# 3310.net
KiCad netlist of a schematic drawn in EAGLE
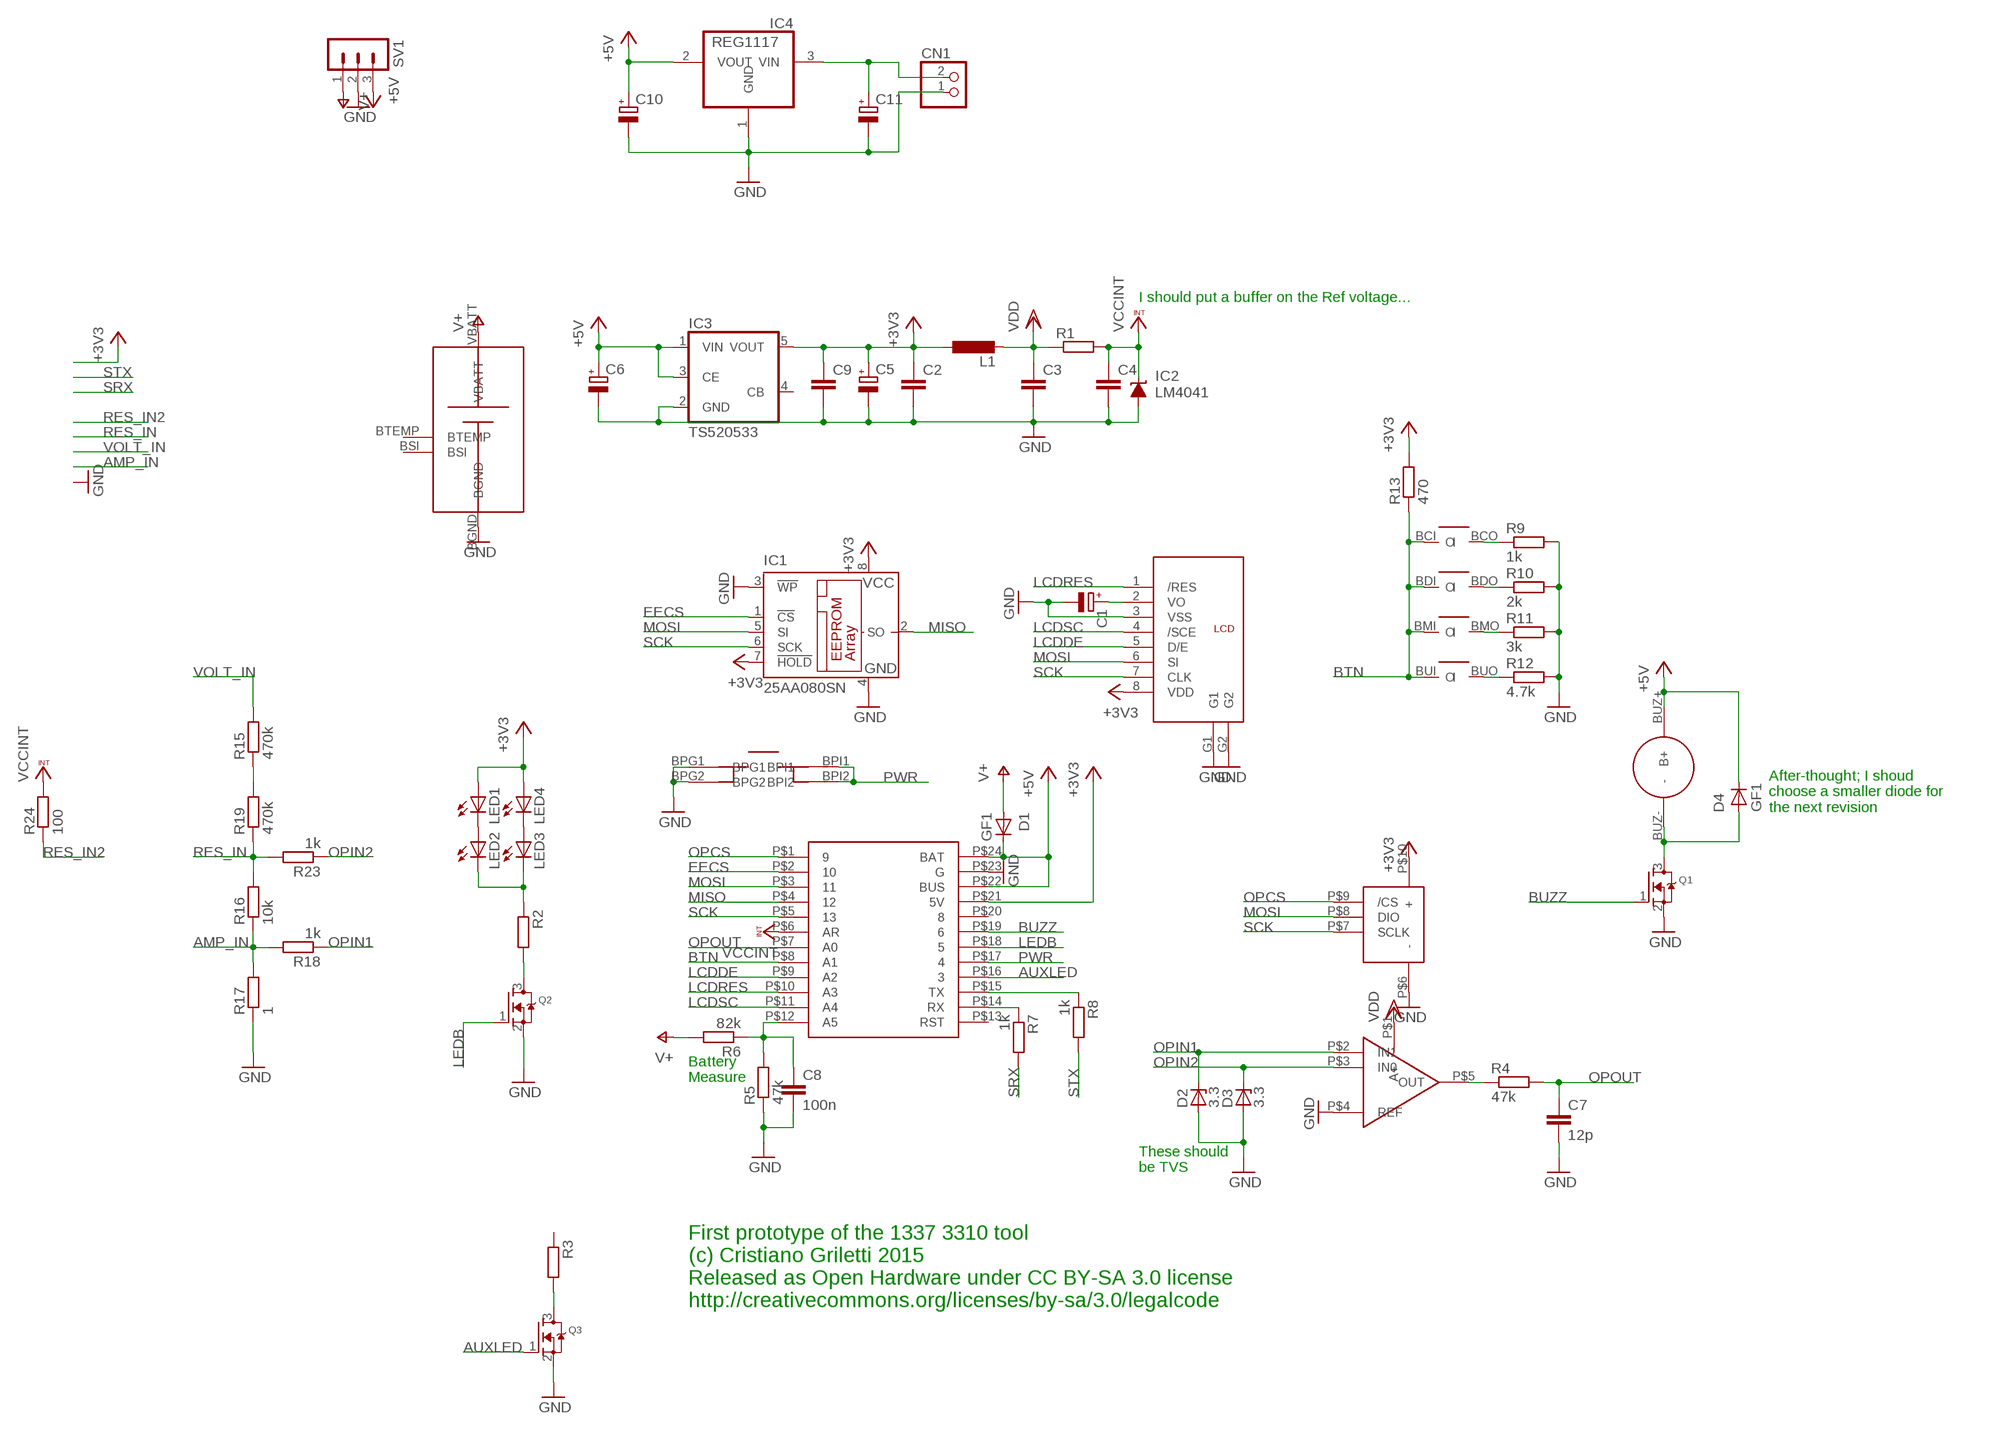
[diagram p0: schematic, sheet 1]

(export (version "E")
  (design (tool "Eeschema 10.0.6"))
  (components
    (comp (ref "C1")
      (value "CPOL-EUC/6032-28R")
      (footprint "eagle-import:C_6032-28R")
      (libsource (lib "eagle-import") (part "CPOL-EUC/6032-28R"))
    )
    (comp (ref "C2")
      (value "C-EUC0805K")
      (footprint "eagle-import:C0805K")
      (libsource (lib "eagle-import") (part "C-EUC0805K"))
    )
    (comp (ref "C3")
      (value "C-EUC0805K")
      (footprint "eagle-import:C0805K")
      (libsource (lib "eagle-import") (part "C-EUC0805K"))
    )
    (comp (ref "C4")
      (value "C-EUC0805K")
      (footprint "eagle-import:C0805K")
      (libsource (lib "eagle-import") (part "C-EUC0805K"))
    )
    (comp (ref "C5")
      (value "CPOL-EUB/3528-21R")
      (footprint "eagle-import:B_3528-21R")
      (libsource (lib "eagle-import") (part "CPOL-EUB/3528-21R"))
    )
    (comp (ref "C6")
      (value "CPOL-EUB/3528-21R")
      (footprint "eagle-import:B_3528-21R")
      (libsource (lib "eagle-import") (part "CPOL-EUB/3528-21R"))
    )
    (comp (ref "C7")
      (value "12p")
      (footprint "eagle-import:C0805K")
      (libsource (lib "eagle-import") (part "C-EUC0805K"))
    )
    (comp (ref "C8")
      (value "100n")
      (footprint "eagle-import:C0805K")
      (libsource (lib "eagle-import") (part "C-EUC0805K"))
    )
    (comp (ref "C9")
      (value "C-EUC0805K")
      (footprint "eagle-import:C0805K")
      (libsource (lib "eagle-import") (part "C-EUC0805K"))
    )
    (comp (ref "C10")
      (value "CPOL-EUB/3528-21R")
      (footprint "eagle-import:B_3528-21R")
      (libsource (lib "eagle-import") (part "CPOL-EUB/3528-21R"))
    )
    (comp (ref "C11")
      (value "CPOL-EUB/3528-21R")
      (footprint "eagle-import:B_3528-21R")
      (libsource (lib "eagle-import") (part "CPOL-EUB/3528-21R"))
    )
    (comp (ref "CN1")
      (value "JST_2PIN-SMT")
      (footprint "eagle-import:JST-PH-2-SMT")
      (libsource (lib "eagle-import") (part "JST_2PIN-SMT"))
    )
    (comp (ref "D1")
      (value "GF1")
      (footprint "eagle-import:SMA-DO214AC")
      (libsource (lib "eagle-import") (part "GF1"))
    )
    (comp (ref "D2")
      (value "3.3")
      (footprint "eagle-import:SOD80C")
      (libsource (lib "eagle-import") (part "ZENER-DIODESOD80C"))
    )
    (comp (ref "D3")
      (value "3.3")
      (footprint "eagle-import:SOD80C")
      (libsource (lib "eagle-import") (part "ZENER-DIODESOD80C"))
    )
    (comp (ref "D4")
      (value "GF1")
      (footprint "eagle-import:SMA-DO214AC")
      (libsource (lib "eagle-import") (part "GF1"))
    )
    (comp (ref "IC1")
      (value "25AA080SN")
      (footprint "eagle-import:SO-08")
      (fields (field (name "MF") "MICROCHIP") (field (name "MPN") "25AA080/SN"))
      (libsource (lib "eagle-import") (part "25SNAA080"))
    )
    (comp (ref "IC2")
      (value "LM4041")
      (footprint "eagle-import:DBZ_R-PDSO-G3")
      (fields (field (name "MPN") "LM4041A12IDBZR"))
      (libsource (lib "eagle-import") (part "LM4041DBZA12"))
    )
    (comp (ref "IC3")
      (value "TS520533")
      (footprint "eagle-import:SOT25")
      (libsource (lib "eagle-import") (part "TS520533"))
    )
    (comp (ref "IC4")
      (value "REG1117")
      (footprint "eagle-import:SOT223")
      (libsource (lib "eagle-import") (part "REG1117"))
    )
    (comp (ref "L1")
      (value "L-EUL3216C")
      (footprint "eagle-import:L3216C")
      (libsource (lib "eagle-import") (part "L-EUL3216C"))
    )
    (comp (ref "LED1")
      (value "LEDCHIPLED_0603")
      (footprint "eagle-import:CHIPLED_0603")
      (libsource (lib "eagle-import") (part "LEDCHIPLED_0603"))
    )
    (comp (ref "LED2")
      (value "LEDCHIPLED_0603")
      (footprint "eagle-import:CHIPLED_0603")
      (libsource (lib "eagle-import") (part "LEDCHIPLED_0603"))
    )
    (comp (ref "LED3")
      (value "LEDCHIPLED_0603")
      (footprint "eagle-import:CHIPLED_0603")
      (libsource (lib "eagle-import") (part "LEDCHIPLED_0603"))
    )
    (comp (ref "LED4")
      (value "LEDCHIPLED_0603")
      (footprint "eagle-import:CHIPLED_0603")
      (libsource (lib "eagle-import") (part "LEDCHIPLED_0603"))
    )
    (comp (ref "Q1")
      (value "MOSFET-NREFLOW")
      (footprint "eagle-import:SOT23")
      (libsource (lib "eagle-import") (part "MOSFET-NREFLOW"))
    )
    (comp (ref "Q2")
      (value "MOSFET-NREFLOW")
      (footprint "eagle-import:SOT23")
      (libsource (lib "eagle-import") (part "MOSFET-NREFLOW"))
    )
    (comp (ref "Q3")
      (value "MOSFET-NREFLOW")
      (footprint "eagle-import:SOT23")
      (libsource (lib "eagle-import") (part "MOSFET-NREFLOW"))
    )
    (comp (ref "R1")
      (value "R-EU_R0805")
      (footprint "eagle-import:R0805")
      (libsource (lib "eagle-import") (part "R-EU_R0805"))
    )
    (comp (ref "R2")
      (value "R-EU_R0805")
      (footprint "eagle-import:R0805")
      (libsource (lib "eagle-import") (part "R-EU_R0805"))
    )
    (comp (ref "R3")
      (value "R-EU_R0805")
      (footprint "eagle-import:R0805")
      (libsource (lib "eagle-import") (part "R-EU_R0805"))
    )
    (comp (ref "R4")
      (value "47k")
      (footprint "eagle-import:R0805")
      (libsource (lib "eagle-import") (part "R-EU_R0805"))
    )
    (comp (ref "R5")
      (value "47k")
      (footprint "eagle-import:R0805")
      (libsource (lib "eagle-import") (part "R-EU_R0805"))
    )
    (comp (ref "R6")
      (value "82k")
      (footprint "eagle-import:R0805")
      (libsource (lib "eagle-import") (part "R-EU_R0805"))
    )
    (comp (ref "R7")
      (value "1k")
      (footprint "eagle-import:R0805")
      (libsource (lib "eagle-import") (part "R-EU_R0805"))
    )
    (comp (ref "R8")
      (value "1k")
      (footprint "eagle-import:R0805")
      (libsource (lib "eagle-import") (part "R-EU_R0805"))
    )
    (comp (ref "R9")
      (value "1k")
      (footprint "eagle-import:R0805")
      (libsource (lib "eagle-import") (part "R-EU_R0805"))
    )
    (comp (ref "R10")
      (value "2k")
      (footprint "eagle-import:R0805")
      (libsource (lib "eagle-import") (part "R-EU_R0805"))
    )
    (comp (ref "R11")
      (value "3k")
      (footprint "eagle-import:R0805")
      (libsource (lib "eagle-import") (part "R-EU_R0805"))
    )
    (comp (ref "R12")
      (value "4.7k")
      (footprint "eagle-import:R0805")
      (libsource (lib "eagle-import") (part "R-EU_R0805"))
    )
    (comp (ref "R13")
      (value "470")
      (footprint "eagle-import:R0805")
      (libsource (lib "eagle-import") (part "R-EU_R0805"))
    )
    (comp (ref "R15")
      (value "470k")
      (footprint "eagle-import:R0805")
      (libsource (lib "eagle-import") (part "R-EU_R0805"))
    )
    (comp (ref "R16")
      (value "10k")
      (footprint "eagle-import:R0805")
      (libsource (lib "eagle-import") (part "R-EU_R0805"))
    )
    (comp (ref "R17")
      (value "1")
      (footprint "eagle-import:R0805")
      (libsource (lib "eagle-import") (part "R-EU_R0805"))
    )
    (comp (ref "R18")
      (value "1k")
      (footprint "eagle-import:R0805")
      (libsource (lib "eagle-import") (part "R-EU_R0805"))
    )
    (comp (ref "R19")
      (value "470k")
      (footprint "eagle-import:R0805")
      (libsource (lib "eagle-import") (part "R-EU_R0805"))
    )
    (comp (ref "R23")
      (value "1k")
      (footprint "eagle-import:R0805")
      (libsource (lib "eagle-import") (part "R-EU_R0805"))
    )
    (comp (ref "R24")
      (value "100")
      (footprint "eagle-import:R0805")
      (libsource (lib "eagle-import") (part "R-EU_R0805"))
    )
    (comp (ref "SV1")
      (value "MA03-1")
      (footprint "eagle-import:MA03-1")
      (libsource (lib "eagle-import") (part "MA03-1"))
    )
    (comp (ref "U$1")
      (value "3310PANEL_NONUM")
      (footprint "eagle-import:3310BRD_NONUM")
      (libsource (lib "eagle-import") (part "3310PANEL_NONUM"))
    )
    (comp (ref "U$2")
      (value "PGA113")
      (footprint "eagle-import:VSSOP")
      (libsource (lib "eagle-import") (part "PGA113"))
    )
    (comp (ref "U$3")
      (value "TRINKET")
      (footprint "eagle-import:TRINKET")
      (libsource (lib "eagle-import") (part "TRINKET"))
    )
  )
  (nets
    (net (code "1") (name "+3V3") (class "Default")
      (node (ref "C2") (pin "1") (pinfunction "1_1") (pintype "passive"))
      (node (ref "C5") (pin "+") (pinfunction "+_+") (pintype "passive"))
      (node (ref "C9") (pin "1") (pinfunction "1_1") (pintype "passive"))
      (node (ref "IC1") (pin "7") (pinfunction "~{HOLD}_7") (pintype "input"))
      (node (ref "IC1") (pin "8") (pinfunction "VCC_8") (pintype "power_in"))
      (node (ref "IC3") (pin "5") (pinfunction "VOUT_5") (pintype "passive"))
      (node (ref "L1") (pin "1") (pinfunction "1_1") (pintype "passive"))
      (node (ref "LED1") (pin "A") (pinfunction "A_A") (pintype "passive"))
      (node (ref "LED4") (pin "A") (pinfunction "A_A") (pintype "passive"))
      (node (ref "R13") (pin "2") (pinfunction "2_2") (pintype "passive"))
      (node (ref "U$1") (pin "8") (pinfunction "VDD_8") (pintype "bidirectional"))
      (node (ref "U$2") (pin "P$10") (pinfunction "+_P$10") (pintype "bidirectional"))
      (node (ref "U$3") (pin "P$21") (pinfunction "5V_P$21") (pintype "bidirectional"))
    )
    (net (code "2") (name "+5V") (class "Default")
      (node (ref "C10") (pin "+") (pinfunction "+_+") (pintype "passive"))
      (node (ref "C6") (pin "+") (pinfunction "+_+") (pintype "passive"))
      (node (ref "D1") (pin "K") (pinfunction "C_K") (pintype "passive"))
      (node (ref "D4") (pin "K") (pinfunction "C_K") (pintype "passive"))
      (node (ref "IC3") (pin "1") (pinfunction "VIN_1") (pintype "input"))
      (node (ref "IC3") (pin "3") (pinfunction "CE_3") (pintype "input"))
      (node (ref "IC4") (pin "2") (pinfunction "VOUT_2") (pintype "output"))
      (node (ref "SV1") (pin "3") (pinfunction "3_3") (pintype "passive"))
      (node (ref "U$1") (pin "BUZ+") (pinfunction "B+_BUZ+") (pintype "bidirectional"))
      (node (ref "U$3") (pin "P$22") (pinfunction "BUS_P$22") (pintype "bidirectional"))
      (node (ref "U$3") (pin "P$24") (pinfunction "BAT_P$24") (pintype "bidirectional"))
    )
    (net (code "3") (name "/AMP_IN") (class "Default")
      (node (ref "R16") (pin "1") (pinfunction "1_1") (pintype "passive"))
      (node (ref "R17") (pin "2") (pinfunction "2_2") (pintype "passive"))
      (node (ref "R18") (pin "2") (pinfunction "2_2") (pintype "passive"))
    )
    (net (code "4") (name "/AUXLED") (class "Default")
      (node (ref "Q3") (pin "1") (pinfunction "G_1") (pintype "bidirectional"))
      (node (ref "U$3") (pin "P$16") (pinfunction "3_P$16") (pintype "bidirectional"))
    )
    (net (code "5") (name "/BTN") (class "Default")
      (node (ref "R13") (pin "1") (pinfunction "1_1") (pintype "passive"))
      (node (ref "U$1") (pin "BCI") (pinfunction "I_BCI") (pintype "bidirectional"))
      (node (ref "U$1") (pin "BDI") (pinfunction "I_BDI") (pintype "bidirectional"))
      (node (ref "U$1") (pin "BMI") (pinfunction "I_BMI") (pintype "bidirectional"))
      (node (ref "U$1") (pin "BUI") (pinfunction "I_BUI") (pintype "bidirectional"))
      (node (ref "U$3") (pin "P$8") (pinfunction "A1_P$8") (pintype "bidirectional"))
    )
    (net (code "6") (name "/BUZZ") (class "Default")
      (node (ref "Q1") (pin "1") (pinfunction "G_1") (pintype "bidirectional"))
      (node (ref "U$3") (pin "P$19") (pinfunction "6_P$19") (pintype "bidirectional"))
    )
    (net (code "7") (name "/EECS") (class "Default")
      (node (ref "IC1") (pin "1") (pinfunction "~{CS}_1") (pintype "input"))
      (node (ref "U$3") (pin "P$2") (pinfunction "10_P$2") (pintype "bidirectional"))
    )
    (net (code "8") (name "/LCDDE") (class "Default")
      (node (ref "U$1") (pin "5") (pinfunction "D/E_5") (pintype "bidirectional"))
      (node (ref "U$3") (pin "P$9") (pinfunction "A2_P$9") (pintype "bidirectional"))
    )
    (net (code "9") (name "/LCDRES") (class "Default")
      (node (ref "U$1") (pin "1") (pinfunction "/RES_1") (pintype "bidirectional"))
      (node (ref "U$3") (pin "P$10") (pinfunction "A3_P$10") (pintype "bidirectional"))
    )
    (net (code "10") (name "/LCDSC") (class "Default")
      (node (ref "U$1") (pin "4") (pinfunction "/SCE_4") (pintype "bidirectional"))
      (node (ref "U$3") (pin "P$11") (pinfunction "A4_P$11") (pintype "bidirectional"))
    )
    (net (code "11") (name "/LEDB") (class "Default")
      (node (ref "Q2") (pin "1") (pinfunction "G_1") (pintype "bidirectional"))
      (node (ref "U$3") (pin "P$18") (pinfunction "5_P$18") (pintype "bidirectional"))
    )
    (net (code "12") (name "/MISO") (class "Default")
      (node (ref "IC1") (pin "2") (pinfunction "SO_2") (pintype "bidirectional"))
      (node (ref "U$3") (pin "P$4") (pinfunction "12_P$4") (pintype "bidirectional"))
    )
    (net (code "13") (name "/MOSI") (class "Default")
      (node (ref "IC1") (pin "5") (pinfunction "SI_5") (pintype "input"))
      (node (ref "U$1") (pin "6") (pinfunction "SI_6") (pintype "bidirectional"))
      (node (ref "U$2") (pin "P$8") (pinfunction "DIO_P$8") (pintype "bidirectional"))
      (node (ref "U$3") (pin "P$3") (pinfunction "11_P$3") (pintype "bidirectional"))
    )
    (net (code "14") (name "/OPCS") (class "Default")
      (node (ref "U$2") (pin "P$9") (pinfunction "/CS_P$9") (pintype "bidirectional"))
      (node (ref "U$3") (pin "P$1") (pinfunction "9_P$1") (pintype "bidirectional"))
    )
    (net (code "15") (name "/OPIN1") (class "Default")
      (node (ref "D2") (pin "C") (pinfunction "C_C") (pintype "passive"))
      (node (ref "R18") (pin "1") (pinfunction "1_1") (pintype "passive"))
      (node (ref "U$2") (pin "P$2") (pinfunction "IN1_P$2") (pintype "bidirectional"))
    )
    (net (code "16") (name "/OPIN2") (class "Default")
      (node (ref "D3") (pin "C") (pinfunction "C_C") (pintype "passive"))
      (node (ref "R23") (pin "1") (pinfunction "1_1") (pintype "passive"))
      (node (ref "U$2") (pin "P$3") (pinfunction "IN0_P$3") (pintype "bidirectional"))
    )
    (net (code "17") (name "/OPOUT") (class "Default")
      (node (ref "C7") (pin "1") (pinfunction "1_1") (pintype "passive"))
      (node (ref "R4") (pin "2") (pinfunction "2_2") (pintype "passive"))
      (node (ref "U$3") (pin "P$7") (pinfunction "A0_P$7") (pintype "bidirectional"))
    )
    (net (code "18") (name "/PWR") (class "Default")
      (node (ref "U$1") (pin "BPI1") (pinfunction "BPI1_BPI1") (pintype "bidirectional"))
      (node (ref "U$1") (pin "BPI2") (pinfunction "BPI2_BPI2") (pintype "bidirectional"))
      (node (ref "U$3") (pin "P$17") (pinfunction "4_P$17") (pintype "bidirectional"))
    )
    (net (code "19") (name "/RES_IN") (class "Default")
      (node (ref "R16") (pin "2") (pinfunction "2_2") (pintype "passive"))
      (node (ref "R19") (pin "1") (pinfunction "1_1") (pintype "passive"))
      (node (ref "R23") (pin "2") (pinfunction "2_2") (pintype "passive"))
    )
    (net (code "20") (name "/RES_IN2") (class "Default")
      (node (ref "R24") (pin "1") (pinfunction "1_1") (pintype "passive"))
    )
    (net (code "21") (name "/SCK") (class "Default")
      (node (ref "IC1") (pin "6") (pinfunction "SCK_6") (pintype "input"))
      (node (ref "U$1") (pin "7") (pinfunction "CLK_7") (pintype "bidirectional"))
      (node (ref "U$2") (pin "P$7") (pinfunction "SCLK_P$7") (pintype "bidirectional"))
      (node (ref "U$3") (pin "P$5") (pinfunction "13_P$5") (pintype "bidirectional"))
    )
    (net (code "22") (name "/SRX") (class "Default")
      (node (ref "R7") (pin "2") (pinfunction "2_2") (pintype "passive"))
    )
    (net (code "23") (name "/STX") (class "Default")
      (node (ref "R8") (pin "2") (pinfunction "2_2") (pintype "passive"))
    )
    (net (code "24") (name "/VOLT_IN") (class "Default")
      (node (ref "R15") (pin "2") (pinfunction "2_2") (pintype "passive"))
    )
    (net (code "25") (name "GND") (class "Default")
      (node (ref "C1") (pin "-") (pinfunction "-_-") (pintype "passive"))
      (node (ref "C10") (pin "-") (pinfunction "-_-") (pintype "passive"))
      (node (ref "C11") (pin "-") (pinfunction "-_-") (pintype "passive"))
      (node (ref "C2") (pin "2") (pinfunction "2_2") (pintype "passive"))
      (node (ref "C3") (pin "2") (pinfunction "2_2") (pintype "passive"))
      (node (ref "C4") (pin "2") (pinfunction "2_2") (pintype "passive"))
      (node (ref "C5") (pin "-") (pinfunction "-_-") (pintype "passive"))
      (node (ref "C6") (pin "-") (pinfunction "-_-") (pintype "passive"))
      (node (ref "C7") (pin "2") (pinfunction "2_2") (pintype "passive"))
      (node (ref "C8") (pin "2") (pinfunction "2_2") (pintype "passive"))
      (node (ref "C9") (pin "2") (pinfunction "2_2") (pintype "passive"))
      (node (ref "CN1") (pin "1") (pinfunction "2_1") (pintype "passive"))
      (node (ref "D2") (pin "A") (pinfunction "A_A") (pintype "passive"))
      (node (ref "D3") (pin "A") (pinfunction "A_A") (pintype "passive"))
      (node (ref "IC1") (pin "3") (pinfunction "~{WP}_3") (pintype "input"))
      (node (ref "IC1") (pin "4") (pinfunction "GND_4") (pintype "power_in"))
      (node (ref "IC2") (pin "2") (pinfunction "A_2") (pintype "passive"))
      (node (ref "IC3") (pin "2") (pinfunction "GND_2") (pintype "passive"))
      (node (ref "IC4") (pin "1") (pinfunction "GND_1") (pintype "power_in"))
      (node (ref "Q1") (pin "2") (pinfunction "S_2") (pintype "bidirectional"))
      (node (ref "Q2") (pin "2") (pinfunction "S_2") (pintype "bidirectional"))
      (node (ref "Q3") (pin "2") (pinfunction "S_2") (pintype "bidirectional"))
      (node (ref "R10") (pin "2") (pinfunction "2_2") (pintype "passive"))
      (node (ref "R11") (pin "2") (pinfunction "2_2") (pintype "passive"))
      (node (ref "R12") (pin "2") (pinfunction "2_2") (pintype "passive"))
      (node (ref "R17") (pin "1") (pinfunction "1_1") (pintype "passive"))
      (node (ref "R5") (pin "1") (pinfunction "1_1") (pintype "passive"))
      (node (ref "R9") (pin "2") (pinfunction "2_2") (pintype "passive"))
      (node (ref "SV1") (pin "2") (pinfunction "2_2") (pintype "passive"))
      (node (ref "U$1") (pin "3") (pinfunction "VSS_3") (pintype "bidirectional"))
      (node (ref "U$1") (pin "BGND") (pinfunction "BGND_BGND") (pintype "bidirectional"))
      (node (ref "U$1") (pin "BPG1") (pinfunction "BPG1_BPG1") (pintype "bidirectional"))
      (node (ref "U$1") (pin "BPG2") (pinfunction "BPG2_BPG2") (pintype "bidirectional"))
      (node (ref "U$1") (pin "G1") (pinfunction "G1_G1") (pintype "bidirectional"))
      (node (ref "U$1") (pin "G2") (pinfunction "G2_G2") (pintype "bidirectional"))
      (node (ref "U$2") (pin "P$4") (pinfunction "REF_P$4") (pintype "bidirectional"))
      (node (ref "U$2") (pin "P$6") (pinfunction "-_P$6") (pintype "bidirectional"))
      (node (ref "U$3") (pin "P$23") (pinfunction "G_P$23") (pintype "bidirectional"))
    )
    (net (code "26") (name "Net-(CN1-1)") (class "Default")
      (node (ref "C11") (pin "+") (pinfunction "+_+") (pintype "passive"))
      (node (ref "CN1") (pin "2") (pinfunction "1_2") (pintype "passive"))
      (node (ref "IC4") (pin "3") (pinfunction "VIN_3") (pintype "input"))
    )
    (net (code "27") (name "Net-(LED1-PadC)") (class "Default")
      (node (ref "LED1") (pin "C") (pinfunction "C_C") (pintype "passive"))
      (node (ref "LED2") (pin "A") (pinfunction "A_A") (pintype "passive"))
    )
    (net (code "28") (name "Net-(LED2-PadC)") (class "Default")
      (node (ref "LED2") (pin "C") (pinfunction "C_C") (pintype "passive"))
      (node (ref "LED3") (pin "C") (pinfunction "C_C") (pintype "passive"))
      (node (ref "R2") (pin "1") (pinfunction "1_1") (pintype "passive"))
    )
    (net (code "29") (name "Net-(LED3-PadA)") (class "Default")
      (node (ref "LED3") (pin "A") (pinfunction "A_A") (pintype "passive"))
      (node (ref "LED4") (pin "C") (pinfunction "C_C") (pintype "passive"))
    )
    (net (code "30") (name "Net-(Q1-D)") (class "Default")
      (node (ref "D4") (pin "A") (pinfunction "A_A") (pintype "passive"))
      (node (ref "Q1") (pin "3") (pinfunction "D_3") (pintype "bidirectional"))
      (node (ref "U$1") (pin "BUZ-") (pinfunction "-_BUZ-") (pintype "bidirectional"))
    )
    (net (code "31") (name "Net-(Q2-D)") (class "Default")
      (node (ref "Q2") (pin "3") (pinfunction "D_3") (pintype "bidirectional"))
      (node (ref "R2") (pin "2") (pinfunction "2_2") (pintype "passive"))
    )
    (net (code "32") (name "Net-(Q3-D)") (class "Default")
      (node (ref "Q3") (pin "3") (pinfunction "D_3") (pintype "bidirectional"))
      (node (ref "R3") (pin "2") (pinfunction "2_2") (pintype "passive"))
    )
    (net (code "33") (name "Net-(R15-Pad1)") (class "Default")
      (node (ref "R15") (pin "1") (pinfunction "1_1") (pintype "passive"))
      (node (ref "R19") (pin "2") (pinfunction "2_2") (pintype "passive"))
    )
    (net (code "34") (name "Net-(U$1A-VO)") (class "Default")
      (node (ref "C1") (pin "+") (pinfunction "+_+") (pintype "passive"))
      (node (ref "U$1") (pin "2") (pinfunction "VO_2") (pintype "bidirectional"))
    )
    (net (code "35") (name "Net-(U$1B-O)") (class "Default")
      (node (ref "R9") (pin "1") (pinfunction "1_1") (pintype "passive"))
      (node (ref "U$1") (pin "BCO") (pinfunction "O_BCO") (pintype "bidirectional"))
    )
    (net (code "36") (name "Net-(U$1C-O)") (class "Default")
      (node (ref "R10") (pin "1") (pinfunction "1_1") (pintype "passive"))
      (node (ref "U$1") (pin "BDO") (pinfunction "O_BDO") (pintype "bidirectional"))
    )
    (net (code "37") (name "Net-(U$1D-O)") (class "Default")
      (node (ref "R11") (pin "1") (pinfunction "1_1") (pintype "passive"))
      (node (ref "U$1") (pin "BMO") (pinfunction "O_BMO") (pintype "bidirectional"))
    )
    (net (code "38") (name "Net-(U$1E-O)") (class "Default")
      (node (ref "R12") (pin "1") (pinfunction "1_1") (pintype "passive"))
      (node (ref "U$1") (pin "BUO") (pinfunction "O_BUO") (pintype "bidirectional"))
    )
    (net (code "39") (name "Net-(U$2-OUT)") (class "Default")
      (node (ref "R4") (pin "1") (pinfunction "1_1") (pintype "passive"))
      (node (ref "U$2") (pin "P$5") (pinfunction "OUT_P$5") (pintype "bidirectional"))
    )
    (net (code "40") (name "Net-(U$3-A5)") (class "Default")
      (node (ref "C8") (pin "1") (pinfunction "1_1") (pintype "passive"))
      (node (ref "R5") (pin "2") (pinfunction "2_2") (pintype "passive"))
      (node (ref "R6") (pin "1") (pinfunction "1_1") (pintype "passive"))
      (node (ref "U$3") (pin "P$12") (pinfunction "A5_P$12") (pintype "bidirectional"))
    )
    (net (code "41") (name "Net-(U$3-RX)") (class "Default")
      (node (ref "R7") (pin "1") (pinfunction "1_1") (pintype "passive"))
      (node (ref "U$3") (pin "P$14") (pinfunction "RX_P$14") (pintype "bidirectional"))
    )
    (net (code "42") (name "Net-(U$3-TX)") (class "Default")
      (node (ref "R8") (pin "1") (pinfunction "1_1") (pintype "passive"))
      (node (ref "U$3") (pin "P$15") (pinfunction "TX_P$15") (pintype "bidirectional"))
    )
    (net (code "43") (name "V+") (class "Default")
      (node (ref "D1") (pin "A") (pinfunction "A_A") (pintype "passive"))
      (node (ref "R6") (pin "2") (pinfunction "2_2") (pintype "passive"))
      (node (ref "SV1") (pin "1") (pinfunction "1_1") (pintype "passive"))
      (node (ref "U$1") (pin "VBATT") (pinfunction "VBATT_VBATT") (pintype "bidirectional"))
    )
    (net (code "44") (name "VCCINT") (class "Default")
      (node (ref "C4") (pin "1") (pinfunction "1_1") (pintype "passive"))
      (node (ref "IC2") (pin "1") (pinfunction "C_1") (pintype "passive"))
      (node (ref "R1") (pin "2") (pinfunction "2_2") (pintype "passive"))
      (node (ref "R24") (pin "2") (pinfunction "2_2") (pintype "passive"))
      (node (ref "U$3") (pin "P$6") (pinfunction "AR_P$6") (pintype "bidirectional"))
    )
    (net (code "45") (name "VDD") (class "Default")
      (node (ref "C3") (pin "1") (pinfunction "1_1") (pintype "passive"))
      (node (ref "L1") (pin "2") (pinfunction "2_2") (pintype "passive"))
      (node (ref "R1") (pin "1") (pinfunction "1_1") (pintype "passive"))
      (node (ref "U$2") (pin "P$1") (pinfunction "A+_P$1") (pintype "bidirectional"))
    )
    (net (code "46") (name "unconnected-(IC3-CB-Pad4)") (class "Default")
      (node (ref "IC3") (pin "4") (pinfunction "CB_4") (pintype "input"))
    )
    (net (code "47") (name "unconnected-(R3-Pad1)") (class "Default")
      (node (ref "R3") (pin "1") (pinfunction "1_1") (pintype "passive"))
    )
    (net (code "48") (name "unconnected-(U$1-PadBSI)") (class "Default")
      (node (ref "U$1") (pin "BSI") (pinfunction "BSI_BSI") (pintype "bidirectional"))
    )
    (net (code "49") (name "unconnected-(U$1-PadBTEMP)") (class "Default")
      (node (ref "U$1") (pin "BTEMP") (pinfunction "BTEMP_BTEMP") (pintype "bidirectional"))
    )
    (net (code "50") (name "unconnected-(U$3-8-PadP$20)") (class "Default")
      (node (ref "U$3") (pin "P$20") (pinfunction "8_P$20") (pintype "bidirectional"))
    )
    (net (code "51") (name "unconnected-(U$3-RST-PadP$13)") (class "Default")
      (node (ref "U$3") (pin "P$13") (pinfunction "RST_P$13") (pintype "bidirectional"))
    )
  )
)
